# Power_-_Regulators.net
KiCad netlist of a schematic drawn in Altium Designer
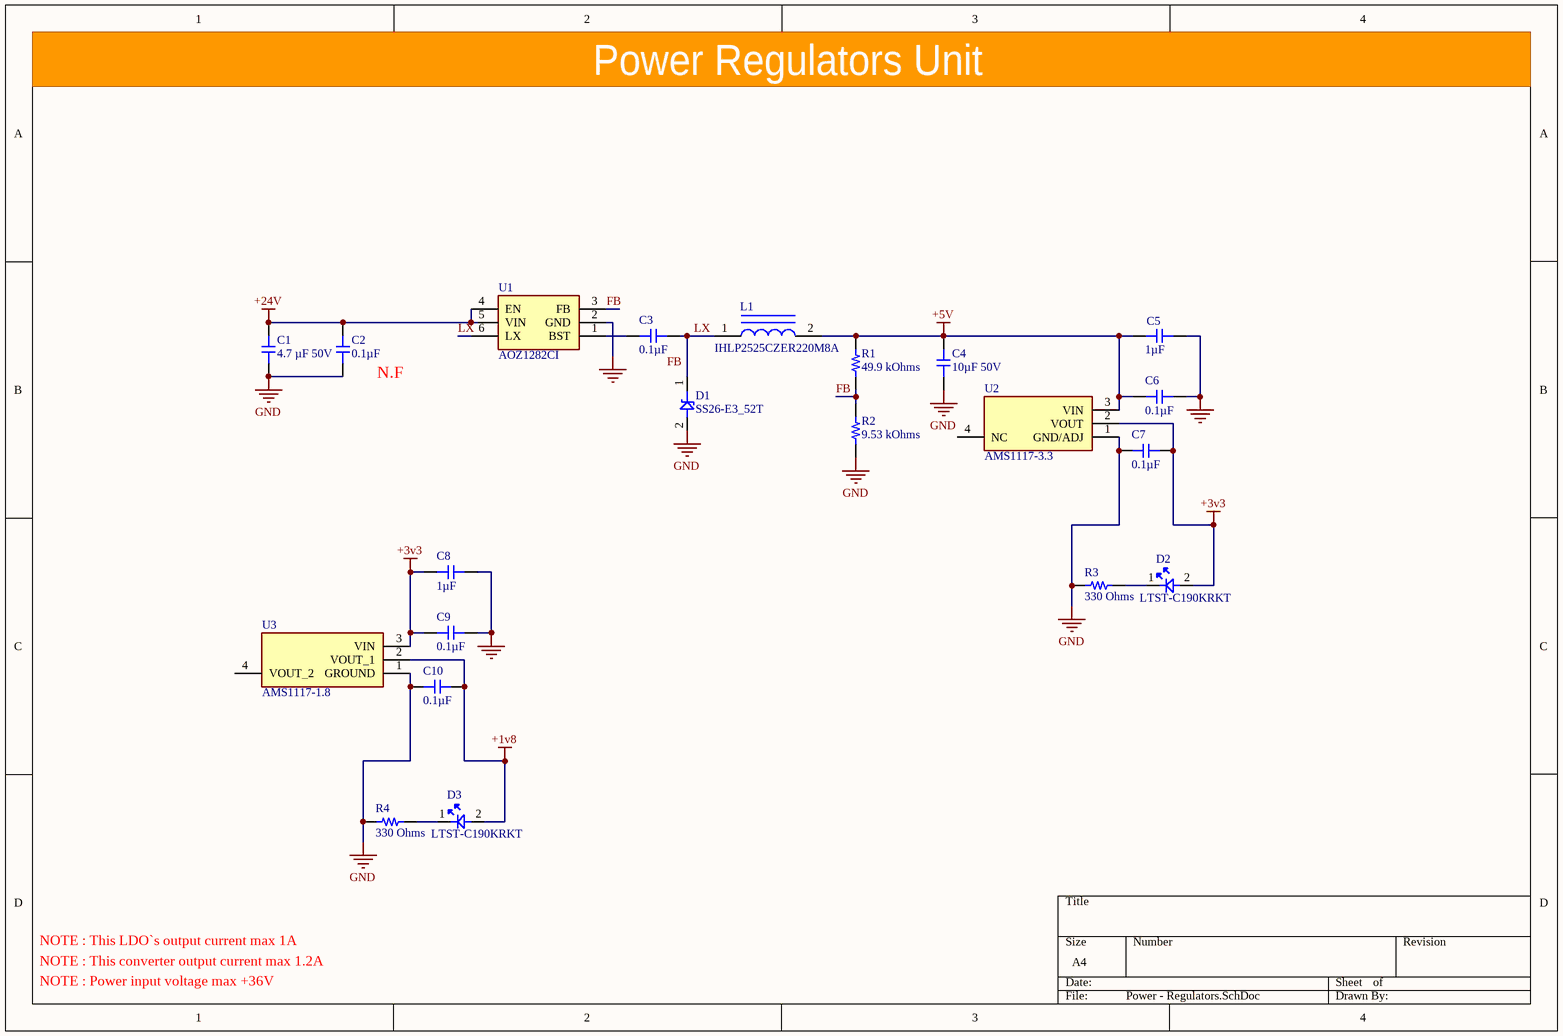
[diagram p0: Power - Regulators.SchDoc]

(export (version "E")
  (design (tool "Eeschema 10.0.6"))
  (components
    (comp (ref "C1")
      (value "4.7 µF 50V")
      (footprint "1206_10uF")
      (description "10 uF 50V 1206")
      (libsource (lib "MainLibrary") (part "4.7 uF 50V 1206"))
    )
    (comp (ref "C2")
      (value "0.1µF")
      (footprint "0805")
      (description "0.1uF 0805 Surface Capacitor")
      (libsource (lib "MainLibrary") (part "0.1uF 0805 Surface Capacitor"))
    )
    (comp (ref "C3")
      (value "0.1µF")
      (footprint "0805")
      (description "0.1uF 0805 Surface Capacitor")
      (libsource (lib "MainLibrary") (part "0.1uF 0805 Surface Capacitor"))
    )
    (comp (ref "C4")
      (value "10µF 50V")
      (footprint "1206_10uF")
      (description "10 uF 50V 1206")
      (libsource (lib "MainLibrary") (part "10 uF 50V 1206"))
    )
    (comp (ref "C5")
      (value "1µF")
      (footprint "0603_Footprint")
      (description "1uF 0603 Surface Capacitor")
      (libsource (lib "MainLibrary") (part "1uF 0603 Surface Capacitor"))
    )
    (comp (ref "C6")
      (value "0.1µF")
      (footprint "0603_Footprint")
      (description "0.1uF 0603 Surface Capacitor")
      (libsource (lib "MainLibrary") (part "0.1uF 0603 Surface Capacitor"))
    )
    (comp (ref "C7")
      (value "0.1µF")
      (footprint "0603_Footprint")
      (description "0.1uF 0603 Surface Capacitor")
      (libsource (lib "MainLibrary") (part "0.1uF 0603 Surface Capacitor"))
    )
    (comp (ref "C8")
      (value "1µF")
      (footprint "0603_Footprint")
      (description "1uF 0603 Surface Capacitor")
      (libsource (lib "MainLibrary") (part "1uF 0603 Surface Capacitor"))
    )
    (comp (ref "C9")
      (value "0.1µF")
      (footprint "0603_Footprint")
      (description "0.1uF 0603 Surface Capacitor")
      (libsource (lib "MainLibrary") (part "0.1uF 0603 Surface Capacitor"))
    )
    (comp (ref "C10")
      (value "0.1µF")
      (footprint "0603_Footprint")
      (description "0.1uF 0603 Surface Capacitor")
      (libsource (lib "MainLibrary") (part "0.1uF 0603 Surface Capacitor"))
    )
    (comp (ref "D1")
      (value "SS26-E3_52T")
      (footprint "DIOM5436X244N")
      (description "Schottky Diode")
      (fields
        (field (name "MANUFACTURER_PART_NUMBER") "SS26-E3/52T")
        (field (name "MOUSER PART NUMBER") "625-SS26-E3")
      )
      (libsource (lib "MainLibrary") (part "SS26-E3_52T"))
    )
    (comp (ref "D2")
      (value "LTST-C190KRKT")
      (footprint "LEDC1608X80N")
      (description "LED")
      (fields (field (name "MOUSER PART NUMBER") "859-LTST-C190KRKT"))
      (libsource (lib "MainLibrary") (part "LTST-C190KRKT"))
    )
    (comp (ref "D3")
      (value "LTST-C190KRKT")
      (footprint "LEDC1608X80N")
      (description "LED")
      (fields (field (name "MOUSER PART NUMBER") "859-LTST-C190KRKT"))
      (libsource (lib "MainLibrary") (part "LTST-C190KRKT"))
    )
    (comp (ref "L1")
      (value "IHLP2525CZER220M8A")
      (footprint "INDPM6965X300N")
      (description "Inductor")
      (fields (field (name "MOUSER PART NUMBER") "70-IHLP2525CZR220M8A"))
      (libsource (lib "MainLibrary") (part "IHLP2525CZER220M8A"))
    )
    (comp (ref "R1")
      (value "49.9 kOhms")
      (footprint "0603_RES")
      (description "49.9 kOhms 0603")
      (libsource (lib "MainLibrary") (part "49.9 kOhms 0603"))
    )
    (comp (ref "R2")
      (value "9.53 kOhms")
      (footprint "0603_RES")
      (description "9.53 kOhms 0603")
      (libsource (lib "MainLibrary") (part "9.53 kOhms 0603"))
    )
    (comp (ref "R3")
      (value "330 Ohms")
      (footprint "0603_RES")
      (description "330 Ohm 0603")
      (libsource (lib "MainLibrary") (part "330 Ohm 0603"))
    )
    (comp (ref "R4")
      (value "330 Ohms")
      (footprint "0603_RES")
      (description "330 Ohm 0603")
      (libsource (lib "MainLibrary") (part "330 Ohm 0603"))
    )
    (comp (ref "U1")
      (value "AOZ1282CI")
      (footprint "SOT95P280X125-6N")
      (description "Integrated Circuit")
      (libsource (lib "MainLibrary") (part "AOZ1282CI"))
    )
    (comp (ref "U2")
      (value "AMS1117-3.3")
      (footprint "SOT229P700X180-4N")
      (description "Integrated Circuit")
      (libsource (lib "MainLibrary") (part "AMS1117-3.3"))
    )
    (comp (ref "U3")
      (value "AMS1117-1.8")
      (footprint "SOT229P700X180-4N")
      (description "Integrated Circuit")
      (libsource (lib "MainLibrary") (part "AMS1117-1.8"))
    )
  )
  (nets
    (net (code "1") (name "+1v8") (class "Default")
      (node (ref "C10") (pin "2") (pinfunction "2_2") (pintype "passive"))
      (node (ref "D3") (pin "2") (pinfunction "A_2") (pintype "passive"))
      (node (ref "U3") (pin "2") (pinfunction "VOUT_1_2") (pintype "passive"))
    )
    (net (code "2") (name "+3v3") (class "Default")
      (node (ref "C7") (pin "2") (pinfunction "2_2") (pintype "passive"))
      (node (ref "C8") (pin "1") (pinfunction "1_1") (pintype "passive"))
      (node (ref "C9") (pin "1") (pinfunction "1_1") (pintype "passive"))
      (node (ref "D2") (pin "2") (pinfunction "A_2") (pintype "passive"))
      (node (ref "U2") (pin "2") (pinfunction "VOUT_2") (pintype "passive"))
      (node (ref "U3") (pin "3") (pinfunction "VIN_3") (pintype "passive"))
    )
    (net (code "3") (name "+5V") (class "Default")
      (node (ref "C4") (pin "1") (pinfunction "1_1") (pintype "passive"))
      (node (ref "C5") (pin "1") (pinfunction "1_1") (pintype "passive"))
      (node (ref "C6") (pin "1") (pinfunction "1_1") (pintype "passive"))
      (node (ref "L1") (pin "2") (pinfunction "2_2") (pintype "passive"))
      (node (ref "R1") (pin "2") (pinfunction "2_2") (pintype "passive"))
      (node (ref "U2") (pin "3") (pinfunction "VIN_3") (pintype "passive"))
    )
    (net (code "4") (name "+24V") (class "Default")
      (node (ref "C1") (pin "1") (pinfunction "1_1") (pintype "passive"))
      (node (ref "C2") (pin "2") (pinfunction "2_2") (pintype "passive"))
      (node (ref "U1") (pin "4") (pinfunction "EN_4") (pintype "passive"))
      (node (ref "U1") (pin "5") (pinfunction "VIN_5") (pintype "passive"))
    )
    (net (code "5") (name "/FB") (class "Default")
      (node (ref "R1") (pin "1") (pinfunction "1_1") (pintype "passive"))
      (node (ref "R2") (pin "2") (pinfunction "2_2") (pintype "passive"))
      (node (ref "U1") (pin "3") (pinfunction "FB_3") (pintype "passive"))
    )
    (net (code "6") (name "/LX") (class "Default")
      (node (ref "C3") (pin "2") (pinfunction "2_2") (pintype "passive"))
      (node (ref "D1") (pin "1") (pinfunction "K_1") (pintype "passive"))
      (node (ref "L1") (pin "1") (pinfunction "1_1") (pintype "passive"))
      (node (ref "U1") (pin "6") (pinfunction "LX_6") (pintype "passive"))
    )
    (net (code "7") (name "GND") (class "Default")
      (node (ref "C1") (pin "2") (pinfunction "2_2") (pintype "passive"))
      (node (ref "C10") (pin "1") (pinfunction "1_1") (pintype "passive"))
      (node (ref "C2") (pin "1") (pinfunction "1_1") (pintype "passive"))
      (node (ref "C4") (pin "2") (pinfunction "2_2") (pintype "passive"))
      (node (ref "C5") (pin "2") (pinfunction "2_2") (pintype "passive"))
      (node (ref "C6") (pin "2") (pinfunction "2_2") (pintype "passive"))
      (node (ref "C7") (pin "1") (pinfunction "1_1") (pintype "passive"))
      (node (ref "C8") (pin "2") (pinfunction "2_2") (pintype "passive"))
      (node (ref "C9") (pin "2") (pinfunction "2_2") (pintype "passive"))
      (node (ref "D1") (pin "2") (pinfunction "A_2") (pintype "passive"))
      (node (ref "R2") (pin "1") (pinfunction "1_1") (pintype "passive"))
      (node (ref "R3") (pin "1") (pinfunction "1_1") (pintype "passive"))
      (node (ref "R4") (pin "1") (pinfunction "1_1") (pintype "passive"))
      (node (ref "U1") (pin "2") (pinfunction "GND_2") (pintype "passive"))
      (node (ref "U2") (pin "1") (pinfunction "GND/ADJ_1") (pintype "passive"))
      (node (ref "U3") (pin "1") (pinfunction "GROUND_1") (pintype "passive"))
    )
    (net (code "8") (name "Net-(D2-K)") (class "Default")
      (node (ref "D2") (pin "1") (pinfunction "K_1") (pintype "passive"))
      (node (ref "R3") (pin "2") (pinfunction "2_2") (pintype "passive"))
    )
    (net (code "9") (name "Net-(D3-K)") (class "Default")
      (node (ref "D3") (pin "1") (pinfunction "K_1") (pintype "passive"))
      (node (ref "R4") (pin "2") (pinfunction "2_2") (pintype "passive"))
    )
    (net (code "10") (name "Net-(U1-BST)") (class "Default")
      (node (ref "C3") (pin "1") (pinfunction "1_1") (pintype "passive"))
      (node (ref "U1") (pin "1") (pinfunction "BST_1") (pintype "passive"))
    )
    (net (code "11") (name "unconnected-(U2-NC-Pad4)") (class "Default")
      (node (ref "U2") (pin "4") (pinfunction "NC_4") (pintype "passive"))
    )
    (net (code "12") (name "unconnected-(U3-VOUT_2-Pad4)") (class "Default")
      (node (ref "U3") (pin "4") (pinfunction "VOUT_2_4") (pintype "passive"))
    )
  )
)
